# Rocket-Control5.net
KiCad netlist of a schematic drawn in EAGLE
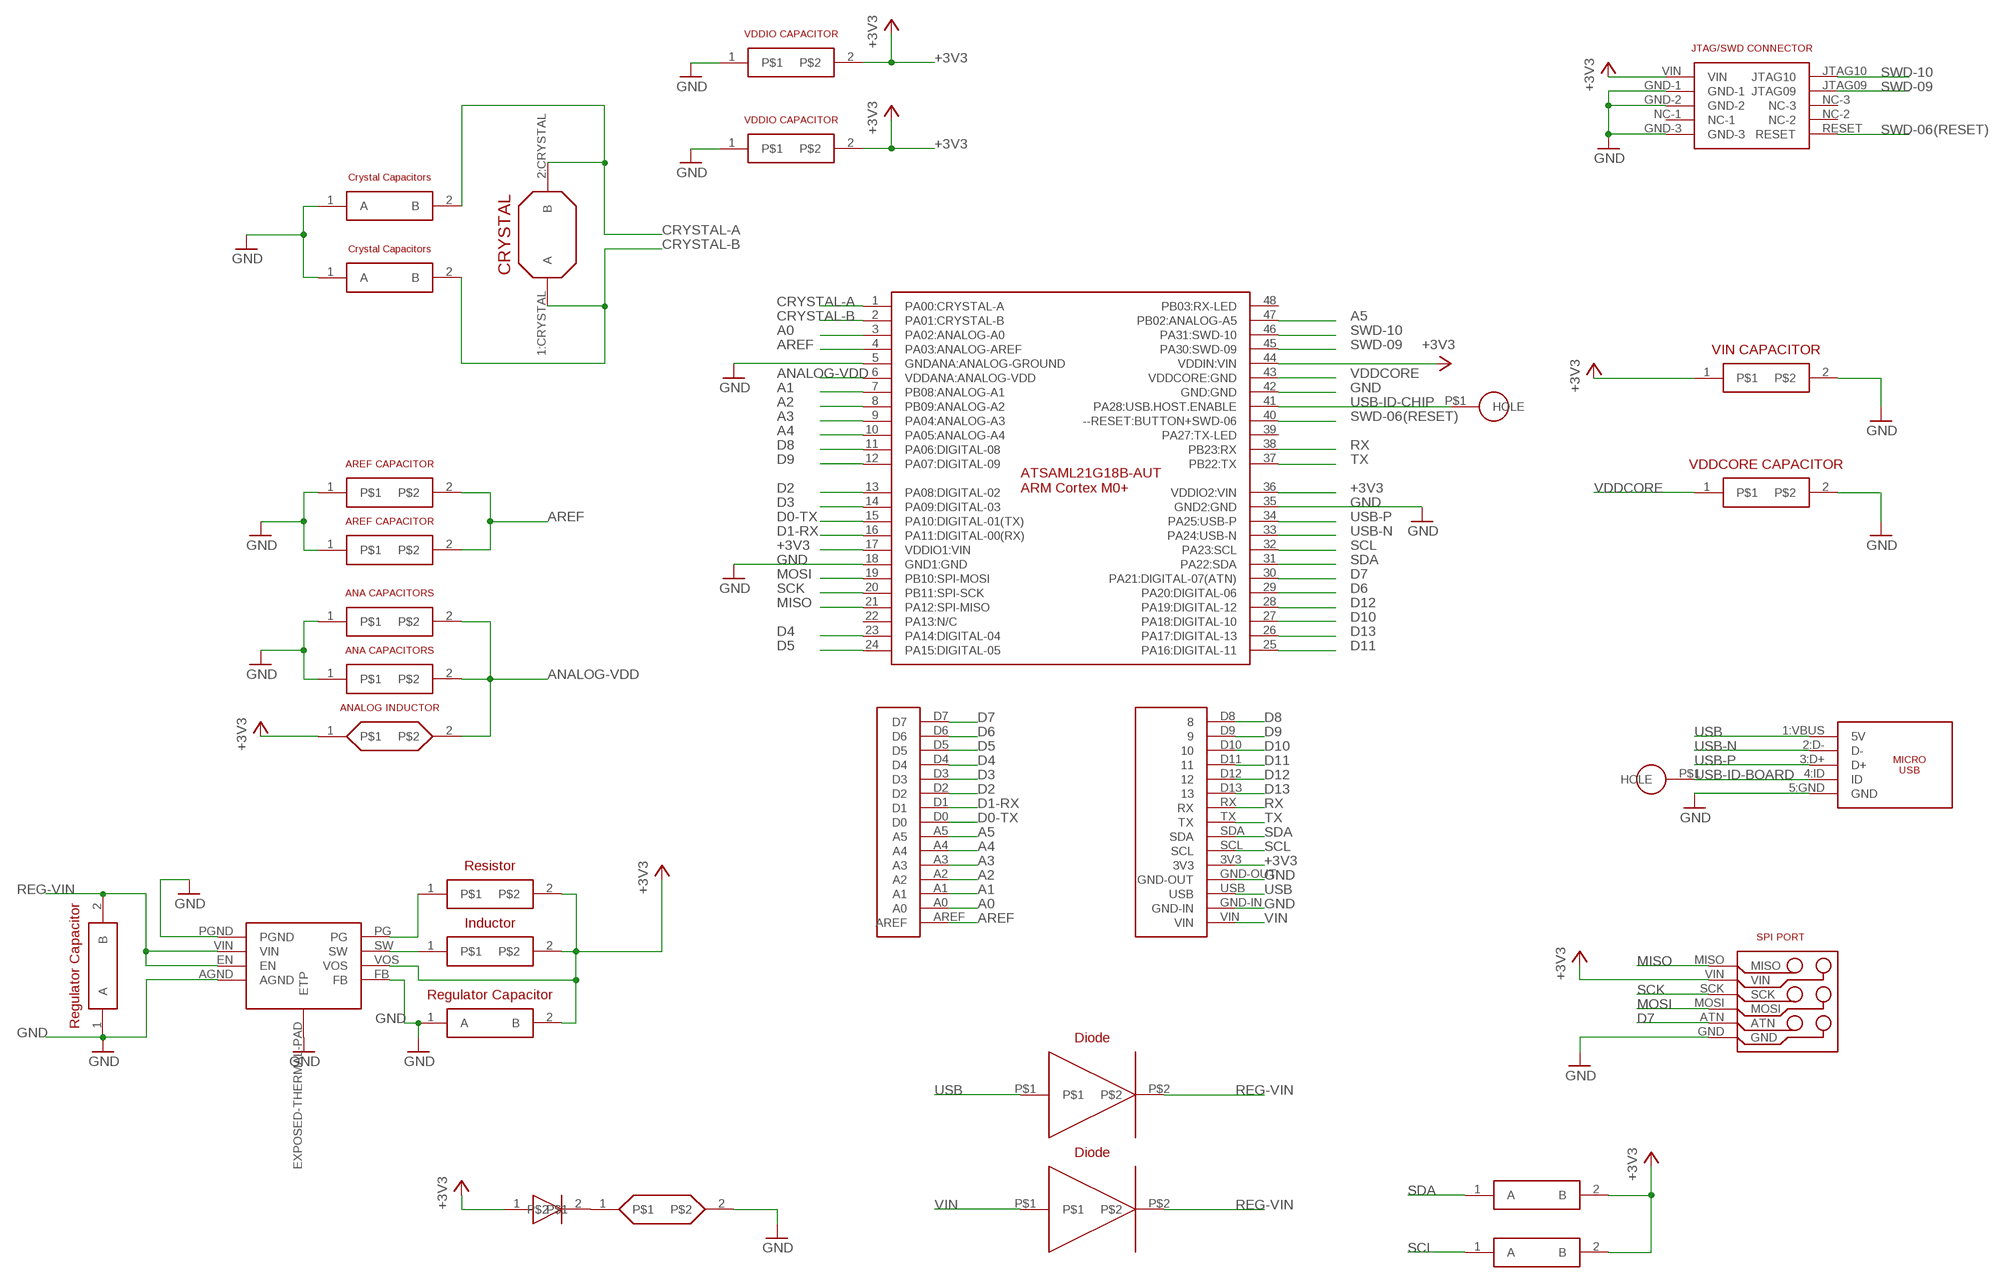
[diagram p0: schematic, sheet 1]

(export (version "E")
  (design (tool "Eeschema 10.0.6"))
  (components
    (comp (ref "U$1")
      (value "ATSAML21G18B-AUT")
      (footprint "eagle-import:TQFP48")
      (libsource (lib "eagle-import") (part "ATSAML21G18B-AUT"))
    )
    (comp (ref "U$2")
      (value "CRYSTAL-CAPACITORS")
      (footprint "eagle-import:C0603")
      (libsource (lib "eagle-import") (part "CRYSTAL-CAPACITORS"))
    )
    (comp (ref "U$3")
      (value "CRYSTAL-CAPACITORS")
      (footprint "eagle-import:C0603")
      (libsource (lib "eagle-import") (part "CRYSTAL-CAPACITORS"))
    )
    (comp (ref "U$4")
      (value "CRYSTAL")
      (footprint "eagle-import:4-SOJ_CRYSTAL")
      (libsource (lib "eagle-import") (part "CRYSTAL"))
    )
    (comp (ref "U$5")
      (value "REGULATOR")
      (footprint "eagle-import:8-WFDFN-EXPOSED-PAD")
      (libsource (lib "eagle-import") (part "REGULATOR"))
    )
    (comp (ref "U$6")
      (value "AREF-CAPACITORS")
      (footprint "eagle-import:C0402")
      (libsource (lib "eagle-import") (part "AREF-CAPACITORS"))
    )
    (comp (ref "U$7")
      (value "AREF-CAPACITORS")
      (footprint "eagle-import:C0402")
      (libsource (lib "eagle-import") (part "AREF-CAPACITORS"))
    )
    (comp (ref "U$8")
      (value "ANALOG-CAPACITORS")
      (footprint "eagle-import:C0402")
      (libsource (lib "eagle-import") (part "ANALOG-CAPACITORS"))
    )
    (comp (ref "U$9")
      (value "ANALOG-CAPACITORS")
      (footprint "eagle-import:C0402")
      (libsource (lib "eagle-import") (part "ANALOG-CAPACITORS"))
    )
    (comp (ref "U$10")
      (value "ANALOG-INDUCTOR")
      (footprint "eagle-import:C0603")
      (libsource (lib "eagle-import") (part "ANALOG-INDUCTOR"))
    )
    (comp (ref "U$11")
      (value "REGULATOR-CAPACITORS")
      (footprint "eagle-import:C0402")
      (libsource (lib "eagle-import") (part "REGULATOR-CAPACITORS"))
    )
    (comp (ref "U$12")
      (value "REGULATOR-CAPACITORS")
      (footprint "eagle-import:C0402")
      (libsource (lib "eagle-import") (part "REGULATOR-CAPACITORS"))
    )
    (comp (ref "U$13")
      (value "REGULATOR-INDUCTOR")
      (footprint "eagle-import:C0603")
      (libsource (lib "eagle-import") (part "REGULATOR-INDUCTOR"))
    )
    (comp (ref "U$14")
      (value "REGULATOR-RESISTOR")
      (footprint "eagle-import:C0603")
      (libsource (lib "eagle-import") (part "REGULATOR-RESISTOR"))
    )
    (comp (ref "U$15")
      (value "REGULATION-DIODE")
      (footprint "eagle-import:SOD-882")
      (libsource (lib "eagle-import") (part "REGULATION-DIODE"))
    )
    (comp (ref "U$16")
      (value "REGULATION-DIODE")
      (footprint "eagle-import:SOD-882")
      (libsource (lib "eagle-import") (part "REGULATION-DIODE"))
    )
    (comp (ref "U$17")
      (value "LED")
      (footprint "eagle-import:C0603")
      (libsource (lib "eagle-import") (part "LED"))
    )
    (comp (ref "U$18")
      (value "LED-RESISTOR")
      (footprint "eagle-import:C0603")
      (libsource (lib "eagle-import") (part "LED-RESISTOR"))
    )
    (comp (ref "U$19")
      (value "I2C-PULLUP")
      (footprint "eagle-import:C0402")
      (libsource (lib "eagle-import") (part "I2C-PULLUP"))
    )
    (comp (ref "U$20")
      (value "I2C-PULLUP")
      (footprint "eagle-import:C0402")
      (libsource (lib "eagle-import") (part "I2C-PULLUP"))
    )
    (comp (ref "U$21")
      (value "HEADER-SIDE-A")
      (footprint "eagle-import:HEADER-SIDE-A")
      (libsource (lib "eagle-import") (part "HEADER-SIDE-A"))
    )
    (comp (ref "U$22")
      (value "HEADER-SIDE-B")
      (footprint "eagle-import:HEADER-SIDE-B")
      (libsource (lib "eagle-import") (part "HEADER-SIDE-B"))
    )
    (comp (ref "U$23")
      (value "HEADER-HOLE")
      (footprint "eagle-import:HEADER-HOLE")
      (libsource (lib "eagle-import") (part "HEADER-HOLE"))
    )
    (comp (ref "U$24")
      (value "HEADER-HOLE")
      (footprint "eagle-import:HEADER-HOLE")
      (libsource (lib "eagle-import") (part "HEADER-HOLE"))
    )
    (comp (ref "U$26")
      (value "VDDIO-CAPACITOR")
      (footprint "eagle-import:C0402")
      (libsource (lib "eagle-import") (part "VDDIO-CAPACITOR"))
    )
    (comp (ref "U$35")
      (value "VDDIO-CAPACITOR")
      (footprint "eagle-import:C0402")
      (libsource (lib "eagle-import") (part "VDDIO-CAPACITOR"))
    )
    (comp (ref "U$38")
      (value "10118194-0001LF:MICRO-USB")
      (footprint "eagle-import:10118194-0001LF_MICRO-USB-B")
      (libsource (lib "eagle-import") (part "10118194-0001LF{colon}MICRO-USB"))
    )
    (comp (ref "U$41")
      (value "SPI-PORT")
      (footprint "eagle-import:SPI-PORT")
      (libsource (lib "eagle-import") (part "SPI-PORT"))
    )
    (comp (ref "U$56")
      (value "VDDCORE-CAPACITOR")
      (footprint "eagle-import:C0402")
      (libsource (lib "eagle-import") (part "VDDCORE-CAPACITOR"))
    )
    (comp (ref "U$57")
      (value "VIN-CAPACITOR")
      (footprint "eagle-import:C0402")
      (libsource (lib "eagle-import") (part "VIN-CAPACITOR"))
    )
    (comp (ref "U$61")
      (value "JTAG-MINI")
      (footprint "eagle-import:JTAG-MINI")
      (libsource (lib "eagle-import") (part "JTAG-MINI"))
    )
  )
  (nets
    (net (code "1") (name "+3V3") (class "Default")
      (node (ref "U$1") (pin "17") (pinfunction "VDDIO1:VIN_17") (pintype "bidirectional"))
      (node (ref "U$1") (pin "36") (pinfunction "VDDIO2:VIN_36") (pintype "bidirectional"))
      (node (ref "U$1") (pin "44") (pinfunction "VDDIN:VIN_44") (pintype "bidirectional"))
      (node (ref "U$10") (pin "1") (pinfunction "P$1_1") (pintype "bidirectional"))
      (node (ref "U$12") (pin "2") (pinfunction "B_2") (pintype "bidirectional"))
      (node (ref "U$13") (pin "2") (pinfunction "P$2_2") (pintype "bidirectional"))
      (node (ref "U$14") (pin "2") (pinfunction "P$2_2") (pintype "bidirectional"))
      (node (ref "U$17") (pin "1") (pinfunction "P$1_1") (pintype "bidirectional"))
      (node (ref "U$19") (pin "2") (pinfunction "B_2") (pintype "bidirectional"))
      (node (ref "U$20") (pin "2") (pinfunction "B_2") (pintype "bidirectional"))
      (node (ref "U$22") (pin "3V3") (pinfunction "3V3_3V3") (pintype "bidirectional"))
      (node (ref "U$26") (pin "2") (pinfunction "P$2_2") (pintype "bidirectional"))
      (node (ref "U$35") (pin "2") (pinfunction "P$2_2") (pintype "bidirectional"))
      (node (ref "U$41") (pin "VIN") (pinfunction "VIN_VIN") (pintype "bidirectional"))
      (node (ref "U$5") (pin "VOS") (pinfunction "VOS_VOS") (pintype "bidirectional"))
      (node (ref "U$57") (pin "1") (pinfunction "P$1_1") (pintype "bidirectional"))
      (node (ref "U$61") (pin "VIN") (pinfunction "VIN_VIN") (pintype "bidirectional"))
    )
    (net (code "2") (name "/A0") (class "Default")
      (node (ref "U$1") (pin "3") (pinfunction "PA02:ANALOG-A0_3") (pintype "bidirectional"))
      (node (ref "U$21") (pin "A0") (pinfunction "A0_A0") (pintype "bidirectional"))
    )
    (net (code "3") (name "/A1") (class "Default")
      (node (ref "U$1") (pin "7") (pinfunction "PB08:ANALOG-A1_7") (pintype "bidirectional"))
      (node (ref "U$21") (pin "A1") (pinfunction "A1_A1") (pintype "bidirectional"))
    )
    (net (code "4") (name "/A2") (class "Default")
      (node (ref "U$1") (pin "8") (pinfunction "PB09:ANALOG-A2_8") (pintype "bidirectional"))
      (node (ref "U$21") (pin "A2") (pinfunction "A2_A2") (pintype "bidirectional"))
    )
    (net (code "5") (name "/A3") (class "Default")
      (node (ref "U$1") (pin "9") (pinfunction "PA04:ANALOG-A3_9") (pintype "bidirectional"))
      (node (ref "U$21") (pin "A3") (pinfunction "A3_A3") (pintype "bidirectional"))
    )
    (net (code "6") (name "/A4") (class "Default")
      (node (ref "U$1") (pin "10") (pinfunction "PA05:ANALOG-A4_10") (pintype "bidirectional"))
      (node (ref "U$21") (pin "A4") (pinfunction "A4_A4") (pintype "bidirectional"))
    )
    (net (code "7") (name "/A5") (class "Default")
      (node (ref "U$1") (pin "47") (pinfunction "PB02:ANALOG-A5_47") (pintype "bidirectional"))
      (node (ref "U$21") (pin "A5") (pinfunction "A5_A5") (pintype "bidirectional"))
    )
    (net (code "8") (name "/ANALOG-VDD") (class "Default")
      (node (ref "U$1") (pin "6") (pinfunction "VDDANA:ANALOG-VDD_6") (pintype "bidirectional"))
      (node (ref "U$10") (pin "2") (pinfunction "P$2_2") (pintype "bidirectional"))
      (node (ref "U$8") (pin "2") (pinfunction "P$2_2") (pintype "bidirectional"))
      (node (ref "U$9") (pin "2") (pinfunction "P$2_2") (pintype "bidirectional"))
    )
    (net (code "9") (name "/AREF") (class "Default")
      (node (ref "U$1") (pin "4") (pinfunction "PA03:ANALOG-AREF_4") (pintype "bidirectional"))
      (node (ref "U$21") (pin "AREF") (pinfunction "AREF_AREF") (pintype "bidirectional"))
      (node (ref "U$6") (pin "2") (pinfunction "P$2_2") (pintype "bidirectional"))
      (node (ref "U$7") (pin "2") (pinfunction "P$2_2") (pintype "bidirectional"))
    )
    (net (code "10") (name "/CRYSTAL-A") (class "Default")
      (node (ref "U$1") (pin "1") (pinfunction "PA00:CRYSTAL-A_1") (pintype "bidirectional"))
      (node (ref "U$2") (pin "2") (pinfunction "B_2") (pintype "bidirectional"))
      (node (ref "U$4") (pin "2:CRYSTAL") (pinfunction "B_2:CRYSTAL") (pintype "bidirectional"))
    )
    (net (code "11") (name "/CRYSTAL-B") (class "Default")
      (node (ref "U$1") (pin "2") (pinfunction "PA01:CRYSTAL-B_2") (pintype "bidirectional"))
      (node (ref "U$3") (pin "2") (pinfunction "B_2") (pintype "bidirectional"))
      (node (ref "U$4") (pin "1:CRYSTAL") (pinfunction "A_1:CRYSTAL") (pintype "bidirectional"))
    )
    (net (code "12") (name "/D0-TX") (class "Default")
      (node (ref "U$1") (pin "15") (pinfunction "PA10:DIGITAL-01(TX)_15") (pintype "bidirectional"))
      (node (ref "U$21") (pin "D0") (pinfunction "D0_D0") (pintype "bidirectional"))
    )
    (net (code "13") (name "/D1-RX") (class "Default")
      (node (ref "U$1") (pin "16") (pinfunction "PA11:DIGITAL-00(RX)_16") (pintype "bidirectional"))
      (node (ref "U$21") (pin "D1") (pinfunction "D1_D1") (pintype "bidirectional"))
    )
    (net (code "14") (name "/D2") (class "Default")
      (node (ref "U$1") (pin "13") (pinfunction "PA08:DIGITAL-02_13") (pintype "bidirectional"))
      (node (ref "U$21") (pin "D2") (pinfunction "D2_D2") (pintype "bidirectional"))
    )
    (net (code "15") (name "/D3") (class "Default")
      (node (ref "U$1") (pin "14") (pinfunction "PA09:DIGITAL-03_14") (pintype "bidirectional"))
      (node (ref "U$21") (pin "D3") (pinfunction "D3_D3") (pintype "bidirectional"))
    )
    (net (code "16") (name "/D4") (class "Default")
      (node (ref "U$1") (pin "23") (pinfunction "PA14:DIGITAL-04_23") (pintype "bidirectional"))
      (node (ref "U$21") (pin "D4") (pinfunction "D4_D4") (pintype "bidirectional"))
    )
    (net (code "17") (name "/D5") (class "Default")
      (node (ref "U$1") (pin "24") (pinfunction "PA15:DIGITAL-05_24") (pintype "bidirectional"))
      (node (ref "U$21") (pin "D5") (pinfunction "D5_D5") (pintype "bidirectional"))
    )
    (net (code "18") (name "/D6") (class "Default")
      (node (ref "U$1") (pin "29") (pinfunction "PA20:DIGITAL-06_29") (pintype "bidirectional"))
      (node (ref "U$21") (pin "D6") (pinfunction "D6_D6") (pintype "bidirectional"))
    )
    (net (code "19") (name "/D7") (class "Default")
      (node (ref "U$1") (pin "30") (pinfunction "PA21:DIGITAL-07(ATN)_30") (pintype "bidirectional"))
      (node (ref "U$21") (pin "D7") (pinfunction "D7_D7") (pintype "bidirectional"))
      (node (ref "U$41") (pin "ATN") (pinfunction "ATN_ATN") (pintype "bidirectional"))
    )
    (net (code "20") (name "/D8") (class "Default")
      (node (ref "U$1") (pin "11") (pinfunction "PA06:DIGITAL-08_11") (pintype "bidirectional"))
      (node (ref "U$22") (pin "D8") (pinfunction "8_D8") (pintype "bidirectional"))
    )
    (net (code "21") (name "/D9") (class "Default")
      (node (ref "U$1") (pin "12") (pinfunction "PA07:DIGITAL-09_12") (pintype "bidirectional"))
      (node (ref "U$22") (pin "D9") (pinfunction "9_D9") (pintype "bidirectional"))
    )
    (net (code "22") (name "/D10") (class "Default")
      (node (ref "U$1") (pin "27") (pinfunction "PA18:DIGITAL-10_27") (pintype "bidirectional"))
      (node (ref "U$22") (pin "D10") (pinfunction "10_D10") (pintype "bidirectional"))
    )
    (net (code "23") (name "/D11") (class "Default")
      (node (ref "U$1") (pin "25") (pinfunction "PA16:DIGITAL-11_25") (pintype "bidirectional"))
      (node (ref "U$22") (pin "D11") (pinfunction "11_D11") (pintype "bidirectional"))
    )
    (net (code "24") (name "/D12") (class "Default")
      (node (ref "U$1") (pin "28") (pinfunction "PA19:DIGITAL-12_28") (pintype "bidirectional"))
      (node (ref "U$22") (pin "D12") (pinfunction "12_D12") (pintype "bidirectional"))
    )
    (net (code "25") (name "/D13") (class "Default")
      (node (ref "U$1") (pin "26") (pinfunction "PA17:DIGITAL-13_26") (pintype "bidirectional"))
      (node (ref "U$22") (pin "D13") (pinfunction "13_D13") (pintype "bidirectional"))
    )
    (net (code "26") (name "/MISO") (class "Default")
      (node (ref "U$1") (pin "21") (pinfunction "PA12:SPI-MISO_21") (pintype "bidirectional"))
      (node (ref "U$41") (pin "MISO") (pinfunction "MISO_MISO") (pintype "bidirectional"))
    )
    (net (code "27") (name "/MOSI") (class "Default")
      (node (ref "U$1") (pin "19") (pinfunction "PB10:SPI-MOSI_19") (pintype "bidirectional"))
      (node (ref "U$41") (pin "MOSI") (pinfunction "MOSI_MOSI") (pintype "bidirectional"))
    )
    (net (code "28") (name "/REG-VIN") (class "Default")
      (node (ref "U$11") (pin "2") (pinfunction "B_2") (pintype "bidirectional"))
      (node (ref "U$15") (pin "P$2") (pinfunction "P$2_P$2") (pintype "bidirectional"))
      (node (ref "U$16") (pin "P$2") (pinfunction "P$2_P$2") (pintype "bidirectional"))
      (node (ref "U$5") (pin "EN") (pinfunction "EN_EN") (pintype "bidirectional"))
      (node (ref "U$5") (pin "VIN") (pinfunction "VIN_VIN") (pintype "bidirectional"))
    )
    (net (code "29") (name "/RX") (class "Default")
      (node (ref "U$1") (pin "38") (pinfunction "PB23:RX_38") (pintype "bidirectional"))
      (node (ref "U$22") (pin "RX") (pinfunction "RX_RX") (pintype "bidirectional"))
    )
    (net (code "30") (name "/SCK") (class "Default")
      (node (ref "U$1") (pin "20") (pinfunction "PB11:SPI-SCK_20") (pintype "bidirectional"))
      (node (ref "U$41") (pin "SCK") (pinfunction "SCK_SCK") (pintype "bidirectional"))
    )
    (net (code "31") (name "/SCL") (class "Default")
      (node (ref "U$1") (pin "32") (pinfunction "PA23:SCL_32") (pintype "bidirectional"))
      (node (ref "U$20") (pin "1") (pinfunction "A_1") (pintype "bidirectional"))
      (node (ref "U$22") (pin "SCL") (pinfunction "SCL_SCL") (pintype "bidirectional"))
    )
    (net (code "32") (name "/SDA") (class "Default")
      (node (ref "U$1") (pin "31") (pinfunction "PA22:SDA_31") (pintype "bidirectional"))
      (node (ref "U$19") (pin "1") (pinfunction "A_1") (pintype "bidirectional"))
      (node (ref "U$22") (pin "SDA") (pinfunction "SDA_SDA") (pintype "bidirectional"))
    )
    (net (code "33") (name "/SWD-06(RESET)") (class "Default")
      (node (ref "U$1") (pin "40") (pinfunction "--RESET:BUTTON+SWD-06_40") (pintype "bidirectional"))
      (node (ref "U$61") (pin "RESET") (pinfunction "RESET_RESET") (pintype "bidirectional"))
    )
    (net (code "34") (name "/SWD-09") (class "Default")
      (node (ref "U$1") (pin "45") (pinfunction "PA30:SWD-09_45") (pintype "bidirectional"))
      (node (ref "U$61") (pin "JTAG09") (pinfunction "JTAG09_JTAG09") (pintype "bidirectional"))
    )
    (net (code "35") (name "/SWD-10") (class "Default")
      (node (ref "U$1") (pin "46") (pinfunction "PA31:SWD-10_46") (pintype "bidirectional"))
      (node (ref "U$61") (pin "JTAG10") (pinfunction "JTAG10_JTAG10") (pintype "bidirectional"))
    )
    (net (code "36") (name "/TX") (class "Default")
      (node (ref "U$1") (pin "37") (pinfunction "PB22:TX_37") (pintype "bidirectional"))
      (node (ref "U$22") (pin "TX") (pinfunction "TX_TX") (pintype "bidirectional"))
    )
    (net (code "37") (name "/USB") (class "Default")
      (node (ref "U$15") (pin "P$1") (pinfunction "P$1_P$1") (pintype "bidirectional"))
      (node (ref "U$22") (pin "USB") (pinfunction "USB_USB") (pintype "bidirectional"))
      (node (ref "U$38") (pin "1:VBUS") (pinfunction "5V_1:VBUS") (pintype "bidirectional"))
    )
    (net (code "38") (name "/USB-ID-BOARD") (class "Default")
      (node (ref "U$23") (pin "P$1") (pinfunction "HOLE_P$1") (pintype "bidirectional"))
      (node (ref "U$38") (pin "4:ID") (pinfunction "ID_4:ID") (pintype "bidirectional"))
    )
    (net (code "39") (name "/USB-ID-CHIP") (class "Default")
      (node (ref "U$1") (pin "41") (pinfunction "PA28:USB.HOST.ENABLE_41") (pintype "bidirectional"))
      (node (ref "U$24") (pin "P$1") (pinfunction "HOLE_P$1") (pintype "bidirectional"))
    )
    (net (code "40") (name "/USB-N") (class "Default")
      (node (ref "U$1") (pin "33") (pinfunction "PA24:USB-N_33") (pintype "bidirectional"))
      (node (ref "U$38") (pin "2:D-") (pinfunction "D-_2:D-") (pintype "bidirectional"))
    )
    (net (code "41") (name "/USB-P") (class "Default")
      (node (ref "U$1") (pin "34") (pinfunction "PA25:USB-P_34") (pintype "bidirectional"))
      (node (ref "U$38") (pin "3:D+") (pinfunction "D+_3:D+") (pintype "bidirectional"))
    )
    (net (code "42") (name "/VDDCORE") (class "Default")
      (node (ref "U$1") (pin "43") (pinfunction "VDDCORE:GND_43") (pintype "bidirectional"))
      (node (ref "U$56") (pin "1") (pinfunction "P$1_1") (pintype "bidirectional"))
    )
    (net (code "43") (name "/VIN") (class "Default")
      (node (ref "U$16") (pin "P$1") (pinfunction "P$1_P$1") (pintype "bidirectional"))
      (node (ref "U$22") (pin "VIN") (pinfunction "VIN_VIN") (pintype "bidirectional"))
    )
    (net (code "44") (name "GND") (class "Default")
      (node (ref "U$1") (pin "18") (pinfunction "GND1:GND_18") (pintype "bidirectional"))
      (node (ref "U$1") (pin "35") (pinfunction "GND2:GND_35") (pintype "bidirectional"))
      (node (ref "U$1") (pin "42") (pinfunction "GND:GND_42") (pintype "bidirectional"))
      (node (ref "U$1") (pin "5") (pinfunction "GNDANA:ANALOG-GROUND_5") (pintype "bidirectional"))
      (node (ref "U$11") (pin "1") (pinfunction "A_1") (pintype "bidirectional"))
      (node (ref "U$12") (pin "1") (pinfunction "A_1") (pintype "bidirectional"))
      (node (ref "U$18") (pin "2") (pinfunction "P$2_2") (pintype "bidirectional"))
      (node (ref "U$2") (pin "1") (pinfunction "A_1") (pintype "bidirectional"))
      (node (ref "U$22") (pin "GND-IN") (pinfunction "GND-IN_GND-IN") (pintype "bidirectional"))
      (node (ref "U$22") (pin "GND-OUT") (pinfunction "GND-OUT_GND-OUT") (pintype "bidirectional"))
      (node (ref "U$26") (pin "1") (pinfunction "P$1_1") (pintype "bidirectional"))
      (node (ref "U$3") (pin "1") (pinfunction "A_1") (pintype "bidirectional"))
      (node (ref "U$35") (pin "1") (pinfunction "P$1_1") (pintype "bidirectional"))
      (node (ref "U$38") (pin "5:GND") (pinfunction "GND_5:GND") (pintype "bidirectional"))
      (node (ref "U$41") (pin "GND") (pinfunction "GND_GND") (pintype "bidirectional"))
      (node (ref "U$5") (pin "AGND") (pinfunction "AGND_AGND") (pintype "bidirectional"))
      (node (ref "U$5") (pin "EXPOSED-THERMAL-PAD") (pinfunction "ETP_EXPOSED-THERMAL-PAD") (pintype "bidirectional"))
      (node (ref "U$5") (pin "FB") (pinfunction "FB_FB") (pintype "bidirectional"))
      (node (ref "U$5") (pin "PGND") (pinfunction "PGND_PGND") (pintype "bidirectional"))
      (node (ref "U$56") (pin "2") (pinfunction "P$2_2") (pintype "bidirectional"))
      (node (ref "U$57") (pin "2") (pinfunction "P$2_2") (pintype "bidirectional"))
      (node (ref "U$6") (pin "1") (pinfunction "P$1_1") (pintype "bidirectional"))
      (node (ref "U$61") (pin "GND-1") (pinfunction "GND-1_GND-1") (pintype "bidirectional"))
      (node (ref "U$61") (pin "GND-2") (pinfunction "GND-2_GND-2") (pintype "bidirectional"))
      (node (ref "U$61") (pin "GND-3") (pinfunction "GND-3_GND-3") (pintype "bidirectional"))
      (node (ref "U$7") (pin "1") (pinfunction "P$1_1") (pintype "bidirectional"))
      (node (ref "U$8") (pin "1") (pinfunction "P$1_1") (pintype "bidirectional"))
      (node (ref "U$9") (pin "1") (pinfunction "P$1_1") (pintype "bidirectional"))
    )
    (net (code "45") (name "Net-(U$13-P$1)") (class "Default")
      (node (ref "U$13") (pin "1") (pinfunction "P$1_1") (pintype "bidirectional"))
      (node (ref "U$5") (pin "SW") (pinfunction "SW_SW") (pintype "bidirectional"))
    )
    (net (code "46") (name "Net-(U$14-P$1)") (class "Default")
      (node (ref "U$14") (pin "1") (pinfunction "P$1_1") (pintype "bidirectional"))
      (node (ref "U$5") (pin "PG") (pinfunction "PG_PG") (pintype "bidirectional"))
    )
    (net (code "47") (name "Net-(U$17-P$2)") (class "Default")
      (node (ref "U$17") (pin "2") (pinfunction "P$2_2") (pintype "bidirectional"))
      (node (ref "U$18") (pin "1") (pinfunction "P$1_1") (pintype "bidirectional"))
    )
    (net (code "48") (name "unconnected-(U$1-PA13:N{slash}C-Pad22)") (class "Default")
      (node (ref "U$1") (pin "22") (pinfunction "PA13:N/C_22") (pintype "bidirectional"))
    )
    (net (code "49") (name "unconnected-(U$1-PA27:TX-LED-Pad39)") (class "Default")
      (node (ref "U$1") (pin "39") (pinfunction "PA27:TX-LED_39") (pintype "bidirectional"))
    )
    (net (code "50") (name "unconnected-(U$1-PB03:RX-LED-Pad48)") (class "Default")
      (node (ref "U$1") (pin "48") (pinfunction "PB03:RX-LED_48") (pintype "bidirectional"))
    )
    (net (code "51") (name "unconnected-(U$61-PadNC-1)") (class "Default")
      (node (ref "U$61") (pin "NC-1") (pinfunction "NC-1_NC-1") (pintype "bidirectional"))
    )
    (net (code "52") (name "unconnected-(U$61-PadNC-2)") (class "Default")
      (node (ref "U$61") (pin "NC-2") (pinfunction "NC-2_NC-2") (pintype "bidirectional"))
    )
    (net (code "53") (name "unconnected-(U$61-PadNC-3)") (class "Default")
      (node (ref "U$61") (pin "NC-3") (pinfunction "NC-3_NC-3") (pintype "bidirectional"))
    )
  )
)
